# CH32V307VCT6-R1.net
KiCad netlist of a schematic drawn in Altium Designer
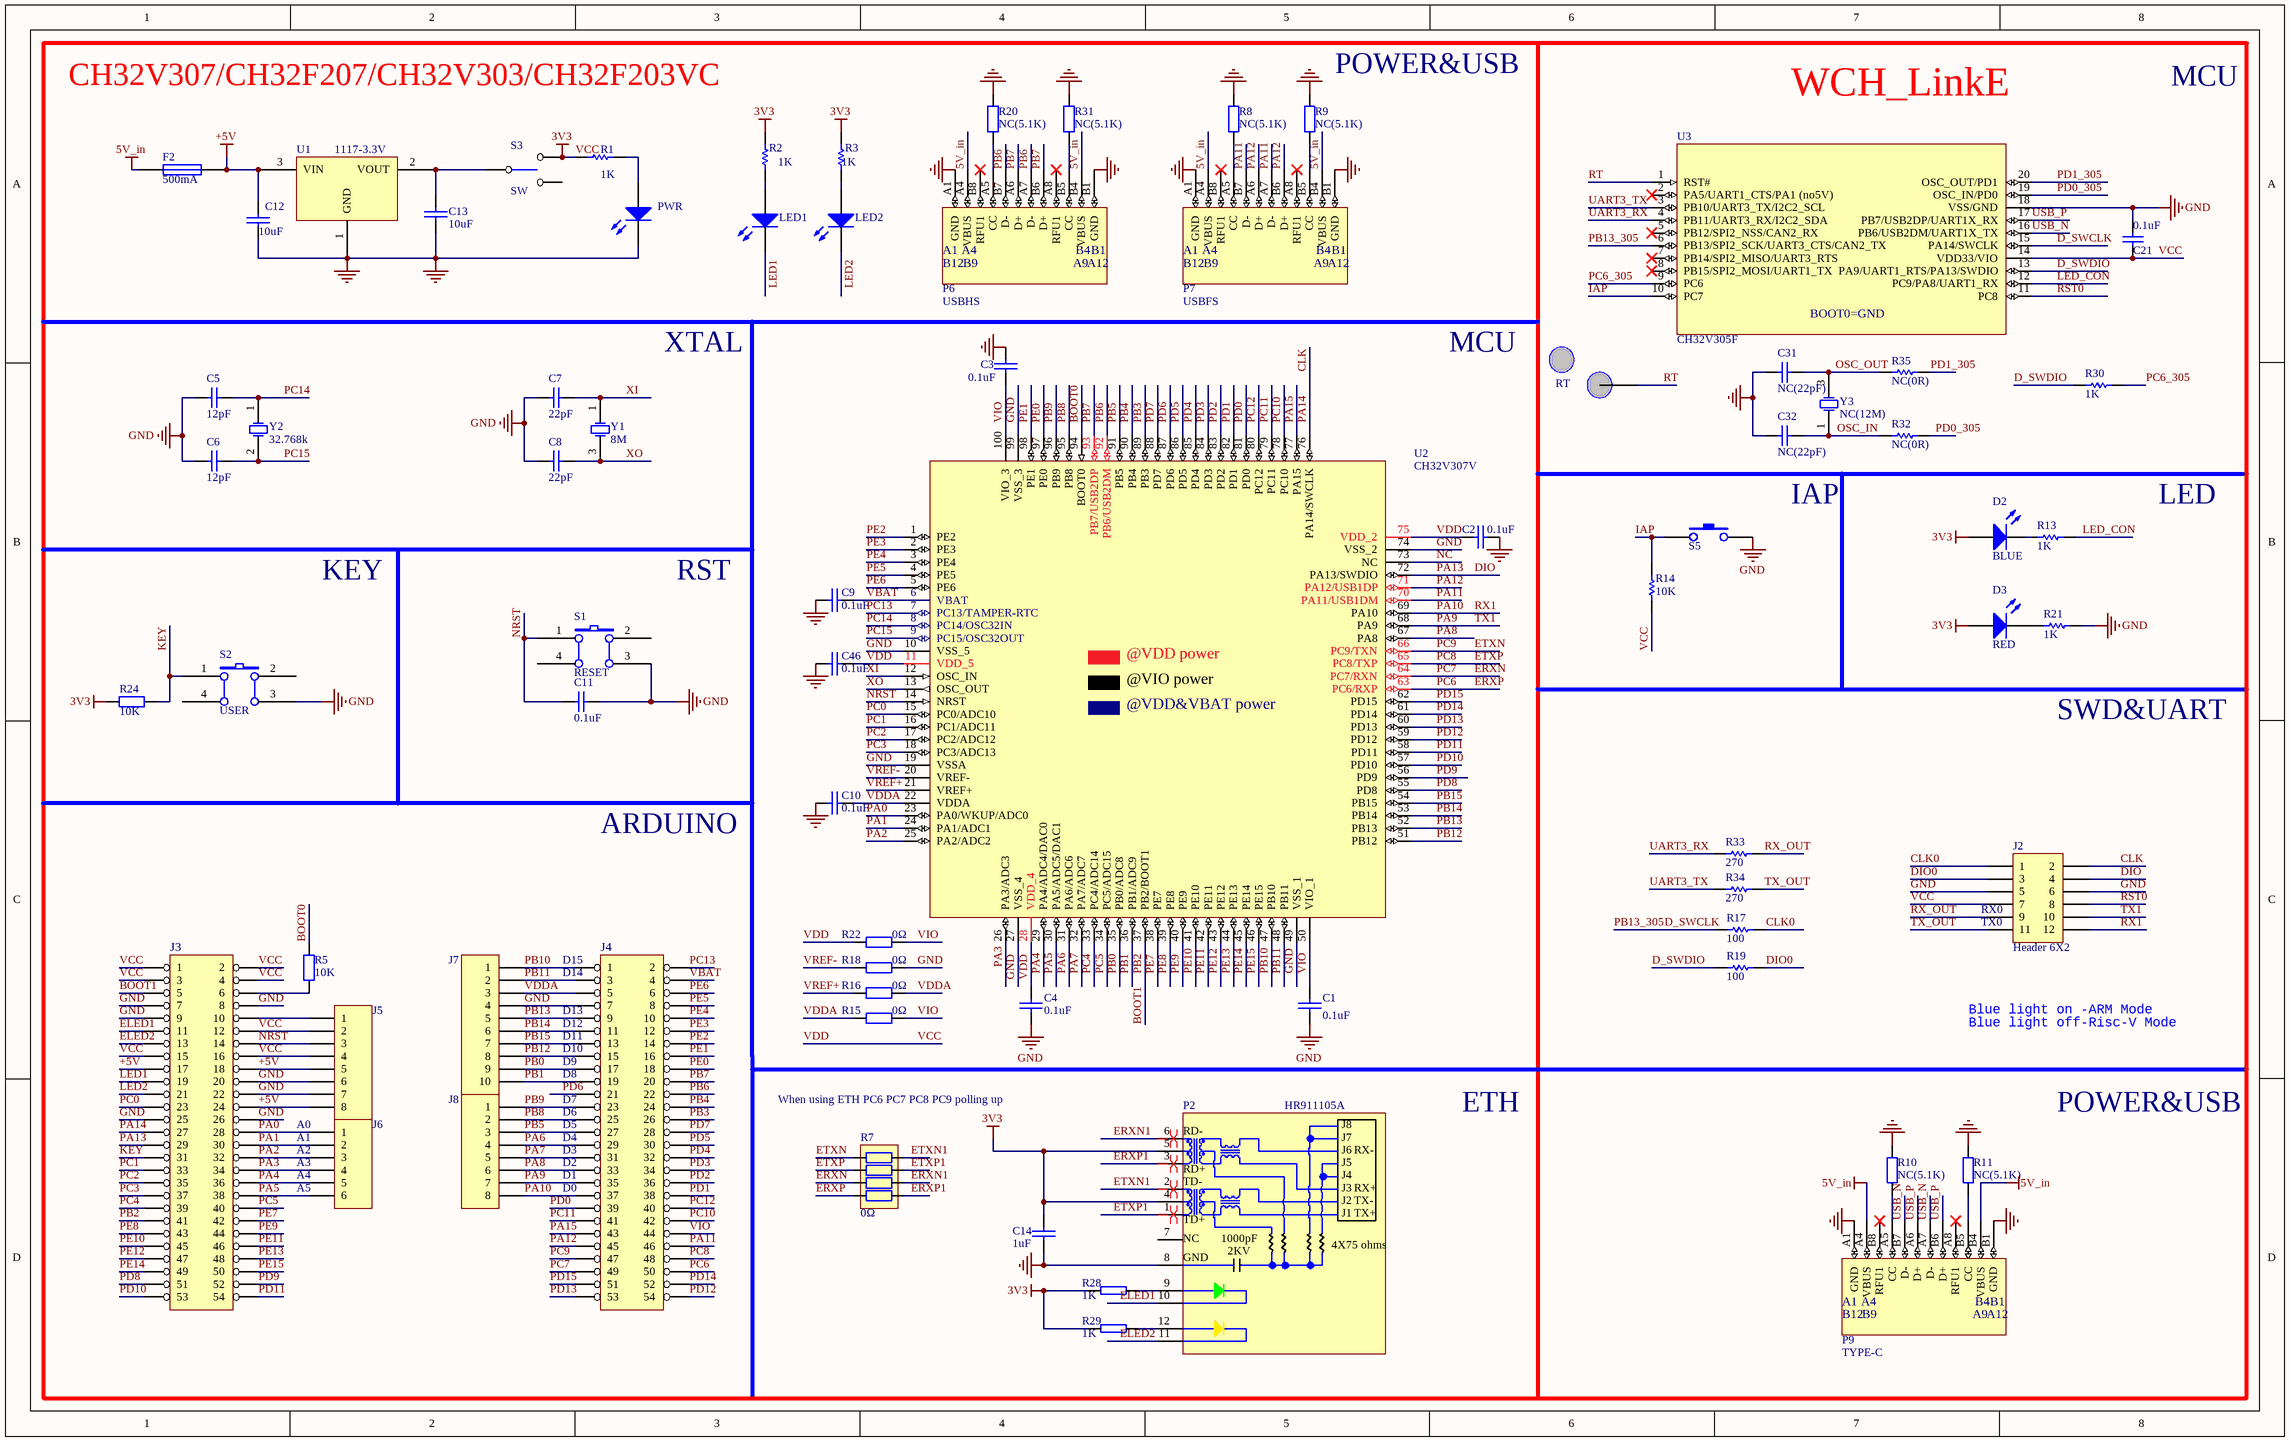
[diagram p0: CH32V307VCT6-R1.SchDoc]

(export (version "E")
  (design (tool "Eeschema 10.0.6"))
  (components
    (comp (ref "C1")
      (value "0.1uF")
      (footprint "0603_C")
      (description "Capacitor")
      (libsource (lib "*") (part "CAP"))
    )
    (comp (ref "C2")
      (value "0.1uF")
      (footprint "0603_C")
      (description "Capacitor")
      (libsource (lib "*") (part "CAP"))
    )
    (comp (ref "C3")
      (value "0.1uF")
      (footprint "0603_C")
      (description "Capacitor")
      (libsource (lib "*") (part "CAP"))
    )
    (comp (ref "C4")
      (value "0.1uF")
      (footprint "0603_C")
      (description "Capacitor")
      (libsource (lib "*") (part "CAP"))
    )
    (comp (ref "C5")
      (value "12pF")
      (footprint "0603_C")
      (description "Capacitor")
      (libsource (lib "Miscellaneous Devices") (part "Cap"))
    )
    (comp (ref "C6")
      (value "12pF")
      (footprint "0603_C")
      (description "Capacitor")
      (libsource (lib "Miscellaneous Devices") (part "Cap"))
    )
    (comp (ref "C7")
      (value "22pF")
      (footprint "0603_C")
      (description "Capacitor")
      (libsource (lib "Miscellaneous Devices") (part "Cap"))
    )
    (comp (ref "C8")
      (value "22pF")
      (footprint "0603_C")
      (description "Capacitor")
      (libsource (lib "Miscellaneous Devices") (part "Cap"))
    )
    (comp (ref "C9")
      (value "0.1uF")
      (footprint "0603_C")
      (description "Capacitor")
      (libsource (lib "*") (part "CAP"))
    )
    (comp (ref "C10")
      (value "0.1uF")
      (footprint "0603_C")
      (description "Capacitor")
      (libsource (lib "*") (part "CAP"))
    )
    (comp (ref "C11")
      (value "0.1uF")
      (footprint "0603_C")
      (description "Capacitor")
      (libsource (lib "Miscellaneous Devices") (part "Cap"))
    )
    (comp (ref "C12")
      (value "10uF")
      (footprint "3216_C")
      (description "Capacitor")
      (libsource (lib "*") (part "CAP"))
    )
    (comp (ref "C13")
      (value "10uF")
      (footprint "3216_C")
      (description "Capacitor")
      (libsource (lib "*") (part "CAP"))
    )
    (comp (ref "C14")
      (value "1uF")
      (footprint "0603_C")
      (description "Capacitor")
      (libsource (lib "*") (part "CAP"))
    )
    (comp (ref "C21")
      (value "0.1uF")
      (footprint "0603_C")
      (description "Capacitor")
      (libsource (lib "Miscellaneous Devices") (part "Cap"))
    )
    (comp (ref "C31")
      (value "NC(22pF)")
      (footprint "0603_C")
      (description "Capacitor")
      (libsource (lib "*") (part "Cap"))
    )
    (comp (ref "C32")
      (value "NC(22pF)")
      (footprint "0603_C")
      (description "Capacitor")
      (libsource (lib "*") (part "Cap"))
    )
    (comp (ref "C46")
      (value "0.1uF")
      (footprint "0603_C")
      (description "Capacitor")
      (libsource (lib "*") (part "CAP"))
    )
    (comp (ref "D2")
      (value "BLUE")
      (footprint "0603+")
      (description "Typical RED, GREEN, YELLOW, AMBER GaAs LED")
      (libsource (lib "MYLIB") (part "D0603"))
    )
    (comp (ref "D3")
      (value "RED")
      (footprint "0603+")
      (description "Typical RED, GREEN, YELLOW, AMBER GaAs LED")
      (libsource (lib "MYLIB") (part "D0603"))
    )
    (comp (ref "F2")
      (value "500mA")
      (footprint "0805")
      (description "Fuse")
      (libsource (lib "*") (part "FUSE1"))
    )
    (comp (ref "J2")
      (value "Header 6X2")
      (footprint "IDC12-2.54mm")
      (description "Header, 6-Pin, Dual row")
      (libsource (lib "Miscellaneous Connectors") (part "Header 6X2"))
    )
    (comp (ref "J3")
      (value "HEADER 27x2")
      (footprint "MYPCB:IDC54-2.54MM")
      (description "Header, 27-Pin, Dual row")
      (libsource (lib "wch_sch_others") (part "HEADER 27x2"))
    )
    (comp (ref "J4")
      (value "HEADER 27x2")
      (footprint "MYPCB:IDC54-2.54MM")
      (description "Header, 27-Pin, Dual row")
      (libsource (lib "wch_sch_others") (part "HEADER 27x2"))
    )
    (comp (ref "J5")
      (value "Header 8")
      (footprint "SIP8-2.54mm")
      (description "Header, 8-Pin")
      (libsource (lib "") (part "Header 8_1"))
    )
    (comp (ref "J6")
      (value "Header 6")
      (footprint "SIP6-2.54MM")
      (description "Header, 6-Pin")
      (libsource (lib "Miscellaneous Connectors") (part "Header 6"))
    )
    (comp (ref "J7")
      (value "Header 10")
      (footprint "SIP10-2.54mm")
      (description "Header, 10-Pin")
      (libsource (lib "Miscellaneous Connectors") (part "Header 10"))
    )
    (comp (ref "J8")
      (value "Header 8")
      (footprint "SIP8-2.54mm")
      (description "Header, 8-Pin")
      (libsource (lib "Miscellaneous Connectors") (part "Header 8"))
    )
    (comp (ref "LED1")
      (value "LED1   blue")
      (footprint "0603+")
      (description "Typical INFRARED GaAs LED")
      (libsource (lib "Miscellaneous Devices") (part "LED0"))
    )
    (comp (ref "LED2")
      (value "LED2  blue")
      (footprint "0603+")
      (description "Typical INFRARED GaAs LED")
      (libsource (lib "Miscellaneous Devices") (part "LED0"))
    )
    (comp (ref "P2") (value "HR911105A") (footprint "HR911105A") (libsource (lib "*") (part "HR911105A")))
    (comp (ref "P6")
      (value "USBHS")
      (footprint "TYPE-C-Receptacle-2.0")
      (libsource (lib "*") (part "TYPE-C1"))
    )
    (comp (ref "P7")
      (value "USBFS")
      (footprint "TYPE-C-Receptacle-2.0")
      (libsource (lib "*") (part "TYPE-C1"))
    )
    (comp (ref "P9")
      (value "TYPE-C")
      (footprint "TYPE-C-Receptacle-2.0")
      (libsource (lib "*") (part "TYPE-C1"))
    )
    (comp (ref "PWR")
      (value "POWER  red")
      (footprint "0603+")
      (description "Typical INFRARED GaAs LED")
      (libsource (lib "Miscellaneous Devices") (part "LED0"))
    )
    (comp (ref "R1")
      (value "1K")
      (footprint "0603")
      (description "Semiconductor Resistor")
      (libsource (lib "Miscellaneous Devices") (part "Res Semi"))
    )
    (comp (ref "R2")
      (value "1K")
      (footprint "0603")
      (description "Semiconductor Resistor")
      (libsource (lib "Miscellaneous Devices") (part "Res Semi"))
    )
    (comp (ref "R3")
      (value "1K")
      (footprint "0603")
      (description "Semiconductor Resistor")
      (libsource (lib "Miscellaneous Devices") (part "Res Semi"))
    )
    (comp (ref "R5")
      (value "10K")
      (footprint "0603")
      (description "Resistor")
      (libsource (lib "Miscellaneous Devices") (part "Res2"))
    )
    (comp (ref "R7")
      (value "0Ω")
      (footprint "RCA-8P4R-0603")
      (description "贴片网络排阻")
      (libsource (lib "wch_sch_others") (part "R-8P4R"))
    )
    (comp (ref "R8")
      (value "NC(5.1K)")
      (footprint "0603")
      (description "Resistor")
      (libsource (lib "") (part "Res2_1"))
    )
    (comp (ref "R9")
      (value "NC(5.1K)")
      (footprint "0603")
      (description "Resistor")
      (libsource (lib "") (part "Res2_1"))
    )
    (comp (ref "R10")
      (value "NC(5.1K)")
      (footprint "0603")
      (description "Resistor")
      (libsource (lib "Miscellaneous Devices") (part "Res2"))
    )
    (comp (ref "R11")
      (value "NC(5.1K)")
      (footprint "0603")
      (description "Resistor")
      (libsource (lib "Miscellaneous Devices") (part "Res2"))
    )
    (comp (ref "R13")
      (value "1K")
      (footprint "0603")
      (description "Resistor")
      (libsource (lib "MYLIB") (part "0603-1"))
    )
    (comp (ref "R14")
      (value "10K")
      (footprint "0603")
      (description "Resistor")
      (libsource (lib "MYLIB") (part "0603-1"))
    )
    (comp (ref "R15")
      (value "0Ω")
      (footprint "0603")
      (description "Resistor")
      (libsource (lib "") (part "Res2_2"))
    )
    (comp (ref "R16")
      (value "0Ω")
      (footprint "0603")
      (description "Resistor")
      (libsource (lib "") (part "Res2_2"))
    )
    (comp (ref "R17")
      (value "100")
      (footprint "0603")
      (description "Resistor")
      (libsource (lib "MYLIB") (part "0603-1"))
    )
    (comp (ref "R18")
      (value "0Ω")
      (footprint "0603")
      (description "Resistor")
      (libsource (lib "") (part "Res2_2"))
    )
    (comp (ref "R19")
      (value "100")
      (footprint "0603")
      (description "Resistor")
      (libsource (lib "MYLIB") (part "0603-1"))
    )
    (comp (ref "R20")
      (value "NC(5.1K)")
      (footprint "0603")
      (description "Resistor")
      (libsource (lib "") (part "Res2_1"))
    )
    (comp (ref "R21")
      (value "1K")
      (footprint "0603")
      (description "Resistor")
      (libsource (lib "MYLIB") (part "0603-1"))
    )
    (comp (ref "R22")
      (value "0Ω")
      (footprint "0603")
      (description "Resistor")
      (libsource (lib "") (part "Res2_2"))
    )
    (comp (ref "R24")
      (value "10K")
      (footprint "0603")
      (description "Resistor")
      (libsource (lib "") (part "Res2_2"))
    )
    (comp (ref "R28") (value "1K") (footprint "0603") (libsource (lib "wch_sch_others") (part "RES")))
    (comp (ref "R29") (value "1K") (footprint "0603") (libsource (lib "wch_sch_others") (part "RES")))
    (comp (ref "R30")
      (value "1K")
      (footprint "0603")
      (description "Resistor")
      (libsource (lib "MYLIB") (part "0603-1"))
    )
    (comp (ref "R31")
      (value "NC(5.1K)")
      (footprint "0603")
      (description "Resistor")
      (libsource (lib "") (part "Res2_1"))
    )
    (comp (ref "R32")
      (value "NC(0R)")
      (footprint "0603")
      (description "Resistor")
      (libsource (lib "MYLIB") (part "0603-1"))
    )
    (comp (ref "R33")
      (value "270")
      (footprint "0603")
      (description "Resistor")
      (libsource (lib "MYLIB") (part "0603-1"))
    )
    (comp (ref "R34")
      (value "270")
      (footprint "0603")
      (description "Resistor")
      (libsource (lib "MYLIB") (part "0603-1"))
    )
    (comp (ref "R35")
      (value "NC(0R)")
      (footprint "0603")
      (description "Resistor")
      (libsource (lib "MYLIB") (part "0603-1"))
    )
    (comp (ref "RT")
      (value "Testpoint")
      (footprint "TESTPOINT1")
      (description "测试点")
      (libsource (lib "wch_sch_others") (part "Testpoint"))
    )
    (comp (ref "S1")
      (value "RESET")
      (footprint "KEYX")
      (description "SE PUSHBUTTON")
      (libsource (lib "Documents") (part "SW PUSHBUTTON"))
    )
    (comp (ref "S2")
      (value "USER")
      (footprint "KEYX")
      (description "SE PUSHBUTTON")
      (libsource (lib "Documents") (part "SW PUSHBUTTON"))
    )
    (comp (ref "S3") (value "SW") (footprint "SW1") (libsource (lib "MYSCH") (part "SW")))
    (comp (ref "S5") (value "KEY") (footprint "贴片按键") (libsource (lib "*") (part "KEY")))
    (comp (ref "U1")
      (value "1117-3.3V")
      (footprint "SOT-223")
      (libsource (lib "wch_sch_others") (part "1117-3.3V"))
    )
    (comp (ref "U2")
      (value "CH32V307V")
      (footprint "LQFP100")
      (description "RISC-V FPU HD-MCU, 144MHz, USB_480M, USB OTG, 1000M Ethernet MAC, 2*CAN, FSMC+DVP")
      (libsource (lib "CHXXX") (part "CH32V307V"))
    )
    (comp (ref "U3")
      (value "CH32V305F")
      (footprint "TSSOP20")
      (description "RISC-V FPU HD-MCU, 144MHz, USB_480M, CAN, UART*2, SPI")
      (libsource (lib "CHXXX") (part "CH32V305F"))
    )
    (comp (ref "Y1")
      (value "8M")
      (footprint "XT3225")
      (description "Crystal Oscillator")
      (libsource (lib "Miscellaneous Devices") (part "XTAL"))
    )
    (comp (ref "Y2")
      (value "32.768k")
      (footprint "FC-135")
      (description "Crystal Oscillator")
      (libsource (lib "") (part "XTAL_1"))
    )
    (comp (ref "Y3")
      (value "NC(12M)")
      (footprint "XT3225")
      (description "Crystal Oscillator")
      (libsource (lib "*") (part "XTAL"))
    )
  )
  (nets
    (net (code "1") (name "+5V") (class "Default")
      (node (ref "C12") (pin "1") (pinfunction "1_1") (pintype "passive"))
      (node (ref "F2") (pin "2") (pinfunction "2_2") (pintype "passive"))
      (node (ref "J3") (pin "17") (pinfunction "17_17") (pintype "passive"))
      (node (ref "J3") (pin "18") (pinfunction "18_18") (pintype "passive"))
      (node (ref "J3") (pin "24") (pinfunction "24_24") (pintype "passive"))
      (node (ref "J5") (pin "5") (pinfunction "5_5") (pintype "passive"))
      (node (ref "J5") (pin "8") (pinfunction "8_8") (pintype "passive"))
      (node (ref "U1") (pin "3") (pinfunction "VIN_3") (pintype "passive"))
    )
    (net (code "2") (name "/BOOT0") (class "Default")
      (node (ref "R5") (pin "2") (pinfunction "2_2") (pintype "passive"))
      (node (ref "U2") (pin "94") (pinfunction "BOOT0_94") (pintype "input"))
    )
    (net (code "3") (name "/BOOT1") (class "Default")
      (node (ref "J3") (pin "41") (pinfunction "41_41") (pintype "passive"))
      (node (ref "J3") (pin "5") (pinfunction "5_5") (pintype "passive"))
      (node (ref "U2") (pin "37") (pinfunction "PB2/BOOT1_37") (pintype "bidirectional"))
    )
    (net (code "4") (name "/CLK") (class "Default")
      (node (ref "J2") (pin "2") (pinfunction "2_2") (pintype "passive"))
      (node (ref "J3") (pin "27") (pinfunction "27_27") (pintype "passive"))
      (node (ref "U2") (pin "76") (pinfunction "PA14/SWCLK_76") (pintype "bidirectional"))
    )
    (net (code "5") (name "/CLK0") (class "Default")
      (node (ref "J2") (pin "1") (pinfunction "1_1") (pintype "passive"))
      (node (ref "R17") (pin "1") (pinfunction "1_1") (pintype "passive"))
    )
    (net (code "6") (name "/DIO") (class "Default")
      (node (ref "J2") (pin "4") (pinfunction "4_4") (pintype "passive"))
      (node (ref "J3") (pin "29") (pinfunction "29_29") (pintype "passive"))
      (node (ref "U2") (pin "72") (pinfunction "PA13/SWDIO_72") (pintype "bidirectional"))
    )
    (net (code "7") (name "/DIO0") (class "Default")
      (node (ref "J2") (pin "3") (pinfunction "3_3") (pintype "passive"))
      (node (ref "R19") (pin "1") (pinfunction "1_1") (pintype "passive"))
    )
    (net (code "8") (name "/D_SWCLK") (class "Default")
      (node (ref "R17") (pin "2") (pinfunction "2_2") (pintype "passive"))
      (node (ref "U3") (pin "15") (pinfunction "PA14/SWCLK_15") (pintype "bidirectional"))
      (node (ref "U3") (pin "6") (pinfunction "PB13/SPI2_SCK/UART3_CTS/CAN2_TX_6") (pintype "bidirectional"))
    )
    (net (code "9") (name "/D_SWDIO") (class "Default")
      (node (ref "R19") (pin "2") (pinfunction "2_2") (pintype "passive"))
      (node (ref "R30") (pin "1") (pinfunction "1_1") (pintype "passive"))
      (node (ref "U3") (pin "13") (pinfunction "PA9/UART1_RTS/PA13/SWDIO_13") (pintype "bidirectional"))
    )
    (net (code "10") (name "/ELED1") (class "Default")
      (node (ref "J3") (pin "11") (pinfunction "11_11") (pintype "passive"))
      (node (ref "P2") (pin "10") (pintype "passive"))
    )
    (net (code "11") (name "/ELED2") (class "Default")
      (node (ref "J3") (pin "13") (pinfunction "13_13") (pintype "passive"))
      (node (ref "P2") (pin "11") (pintype "passive"))
    )
    (net (code "12") (name "/ERXN") (class "Default")
      (node (ref "J4") (pin "49") (pinfunction "49_49") (pintype "passive"))
      (node (ref "R7") (pin "3") (pinfunction "3_3") (pintype "passive"))
      (node (ref "U2") (pin "64") (pinfunction "PC7/RXN_64") (pintype "bidirectional"))
    )
    (net (code "13") (name "/ERXN1") (class "Default")
      (node (ref "P2") (pin "6") (pintype "passive"))
      (node (ref "R7") (pin "6") (pinfunction "6_6") (pintype "passive"))
    )
    (net (code "14") (name "/ERXP") (class "Default")
      (node (ref "J4") (pin "50") (pinfunction "50_50") (pintype "passive"))
      (node (ref "R7") (pin "4") (pinfunction "4_4") (pintype "passive"))
      (node (ref "U2") (pin "63") (pinfunction "PC6/RXP_63") (pintype "bidirectional"))
    )
    (net (code "15") (name "/ERXP1") (class "Default")
      (node (ref "P2") (pin "3") (pintype "passive"))
      (node (ref "R7") (pin "5") (pinfunction "5_5") (pintype "passive"))
    )
    (net (code "16") (name "/ETXN") (class "Default")
      (node (ref "J4") (pin "47") (pinfunction "47_47") (pintype "passive"))
      (node (ref "R7") (pin "1") (pinfunction "1_1") (pintype "passive"))
      (node (ref "U2") (pin "66") (pinfunction "PC9/TXN_66") (pintype "bidirectional"))
    )
    (net (code "17") (name "/ETXN1") (class "Default")
      (node (ref "P2") (pin "2") (pintype "passive"))
      (node (ref "R7") (pin "8") (pinfunction "8_8") (pintype "passive"))
    )
    (net (code "18") (name "/ETXP") (class "Default")
      (node (ref "J4") (pin "48") (pinfunction "48_48") (pintype "passive"))
      (node (ref "R7") (pin "2") (pinfunction "2_2") (pintype "passive"))
      (node (ref "U2") (pin "65") (pinfunction "PC8/TXP_65") (pintype "bidirectional"))
    )
    (net (code "19") (name "/ETXP1") (class "Default")
      (node (ref "P2") (pin "1") (pintype "passive"))
      (node (ref "R7") (pin "7") (pinfunction "7_7") (pintype "passive"))
    )
    (net (code "20") (name "/IAP") (class "Default")
      (node (ref "R14") (pin "1") (pinfunction "1_1") (pintype "passive"))
      (node (ref "S5") (pin "1") (pinfunction "1_1") (pintype "passive"))
      (node (ref "U3") (pin "10") (pinfunction "PC7_10") (pintype "bidirectional"))
    )
    (net (code "21") (name "/KEY") (class "Default")
      (node (ref "J3") (pin "31") (pinfunction "31_31") (pintype "passive"))
      (node (ref "R24") (pin "1") (pinfunction "1_1") (pintype "passive"))
      (node (ref "S2") (pin "1") (pinfunction "A0_1") (pintype "passive"))
    )
    (net (code "22") (name "/LED1") (class "Default")
      (node (ref "J3") (pin "19") (pinfunction "19_19") (pintype "passive"))
      (node (ref "LED1") (pin "2") (pinfunction "K_2") (pintype "passive"))
    )
    (net (code "23") (name "/LED2") (class "Default")
      (node (ref "J3") (pin "21") (pinfunction "21_21") (pintype "passive"))
      (node (ref "LED2") (pin "2") (pinfunction "K_2") (pintype "passive"))
    )
    (net (code "24") (name "/LED_CON") (class "Default")
      (node (ref "R13") (pin "1") (pinfunction "1_1") (pintype "passive"))
      (node (ref "U3") (pin "12") (pinfunction "PC9/PA8/UART1_RX_12") (pintype "bidirectional"))
    )
    (net (code "25") (name "/NC") (class "Default")
      (node (ref "U2") (pin "73") (pinfunction "NC_73") (pintype "tri_state"))
    )
    (net (code "26") (name "/NRST") (class "Default")
      (node (ref "C11") (pin "2") (pinfunction "2_2") (pintype "passive"))
      (node (ref "J3") (pin "14") (pinfunction "14_14") (pintype "passive"))
      (node (ref "J5") (pin "3") (pinfunction "3_3") (pintype "passive"))
      (node (ref "S1") (pin "1") (pinfunction "A0_1") (pintype "passive"))
      (node (ref "U2") (pin "14") (pinfunction "NRST_14") (pintype "input"))
    )
    (net (code "27") (name "/OSC_IN") (class "Default")
      (node (ref "C32") (pin "2") (pinfunction "2_2") (pintype "passive"))
      (node (ref "R32") (pin "2") (pinfunction "2_2") (pintype "passive"))
      (node (ref "Y3") (pin "1") (pinfunction "OSC1_1") (pintype "passive"))
    )
    (net (code "28") (name "/OSC_OUT") (class "Default")
      (node (ref "C31") (pin "2") (pinfunction "2_2") (pintype "passive"))
      (node (ref "R35") (pin "2") (pinfunction "2_2") (pintype "passive"))
      (node (ref "Y3") (pin "3") (pinfunction "OSC2_3") (pintype "passive"))
    )
    (net (code "29") (name "/PA0") (class "Default")
      (node (ref "J3") (pin "28") (pinfunction "28_28") (pintype "passive"))
      (node (ref "J6") (pin "1") (pinfunction "1_1") (pintype "passive"))
      (node (ref "U2") (pin "23") (pinfunction "PA0/WKUP/ADC0_23") (pintype "bidirectional"))
    )
    (net (code "30") (name "/PA1") (class "Default")
      (node (ref "J3") (pin "30") (pinfunction "30_30") (pintype "passive"))
      (node (ref "J6") (pin "2") (pinfunction "2_2") (pintype "passive"))
      (node (ref "U2") (pin "24") (pinfunction "PA1/ADC1_24") (pintype "bidirectional"))
    )
    (net (code "31") (name "/PA2") (class "Default")
      (node (ref "J3") (pin "32") (pinfunction "32_32") (pintype "passive"))
      (node (ref "J6") (pin "3") (pinfunction "3_3") (pintype "passive"))
      (node (ref "U2") (pin "25") (pinfunction "PA2/ADC2_25") (pintype "bidirectional"))
    )
    (net (code "32") (name "/PA3") (class "Default")
      (node (ref "J3") (pin "34") (pinfunction "34_34") (pintype "passive"))
      (node (ref "J6") (pin "4") (pinfunction "4_4") (pintype "passive"))
      (node (ref "U2") (pin "26") (pinfunction "PA3/ADC3_26") (pintype "bidirectional"))
    )
    (net (code "33") (name "/PA4") (class "Default")
      (node (ref "J3") (pin "36") (pinfunction "36_36") (pintype "passive"))
      (node (ref "J6") (pin "5") (pinfunction "5_5") (pintype "passive"))
      (node (ref "U2") (pin "29") (pinfunction "PA4/ADC4/DAC0_29") (pintype "bidirectional"))
    )
    (net (code "34") (name "/PA5") (class "Default")
      (node (ref "J3") (pin "38") (pinfunction "38_38") (pintype "passive"))
      (node (ref "J6") (pin "6") (pinfunction "6_6") (pintype "passive"))
      (node (ref "U2") (pin "30") (pinfunction "PA5/ADC5/DAC1_30") (pintype "bidirectional"))
    )
    (net (code "35") (name "/PA6") (class "Default")
      (node (ref "J4") (pin "29") (pinfunction "29_29") (pintype "passive"))
      (node (ref "J8") (pin "4") (pinfunction "4_4") (pintype "passive"))
      (node (ref "U2") (pin "31") (pinfunction "PA6/ADC6_31") (pintype "bidirectional"))
    )
    (net (code "36") (name "/PA7") (class "Default")
      (node (ref "J4") (pin "31") (pinfunction "31_31") (pintype "passive"))
      (node (ref "J8") (pin "5") (pinfunction "5_5") (pintype "passive"))
      (node (ref "U2") (pin "32") (pinfunction "PA7/ADC7_32") (pintype "bidirectional"))
    )
    (net (code "37") (name "/PA8") (class "Default")
      (node (ref "J4") (pin "33") (pinfunction "33_33") (pintype "passive"))
      (node (ref "J8") (pin "6") (pinfunction "6_6") (pintype "passive"))
      (node (ref "U2") (pin "67") (pinfunction "PA8_67") (pintype "bidirectional"))
    )
    (net (code "38") (name "/PA9") (class "Default")
      (node (ref "J2") (pin "10") (pinfunction "10_10") (pintype "passive"))
      (node (ref "J4") (pin "35") (pinfunction "35_35") (pintype "passive"))
      (node (ref "J8") (pin "7") (pinfunction "7_7") (pintype "passive"))
      (node (ref "U2") (pin "68") (pinfunction "PA9_68") (pintype "bidirectional"))
    )
    (net (code "39") (name "/PA10") (class "Default")
      (node (ref "J2") (pin "12") (pinfunction "12_12") (pintype "passive"))
      (node (ref "J4") (pin "37") (pinfunction "37_37") (pintype "passive"))
      (node (ref "J8") (pin "8") (pinfunction "8_8") (pintype "passive"))
      (node (ref "U2") (pin "69") (pinfunction "PA10_69") (pintype "bidirectional"))
    )
    (net (code "40") (name "/PA11") (class "Default")
      (node (ref "J4") (pin "46") (pinfunction "46_46") (pintype "passive"))
      (node (ref "P7") (pin "A7") (pinfunction "D-_A7") (pintype "bidirectional"))
      (node (ref "P7") (pin "B7") (pinfunction "D-_B7") (pintype "bidirectional"))
      (node (ref "U2") (pin "70") (pinfunction "PA11/USB1DM_70") (pintype "bidirectional"))
    )
    (net (code "41") (name "/PA12") (class "Default")
      (node (ref "J4") (pin "45") (pinfunction "45_45") (pintype "passive"))
      (node (ref "P7") (pin "A6") (pinfunction "D+_A6") (pintype "bidirectional"))
      (node (ref "P7") (pin "B6") (pinfunction "D+_B6") (pintype "bidirectional"))
      (node (ref "U2") (pin "71") (pinfunction "PA12/USB1DP_71") (pintype "bidirectional"))
    )
    (net (code "42") (name "/PA15") (class "Default")
      (node (ref "J4") (pin "43") (pinfunction "43_43") (pintype "passive"))
      (node (ref "U2") (pin "77") (pinfunction "PA15_77") (pintype "bidirectional"))
    )
    (net (code "43") (name "/PB0") (class "Default")
      (node (ref "J4") (pin "17") (pinfunction "17_17") (pintype "passive"))
      (node (ref "J7") (pin "9") (pinfunction "9_9") (pintype "passive"))
      (node (ref "U2") (pin "35") (pinfunction "PB0/ADC8_35") (pintype "bidirectional"))
    )
    (net (code "44") (name "/PB1") (class "Default")
      (node (ref "J4") (pin "19") (pinfunction "19_19") (pintype "passive"))
      (node (ref "J7") (pin "10") (pinfunction "10_10") (pintype "passive"))
      (node (ref "U2") (pin "36") (pinfunction "PB1/ADC9_36") (pintype "bidirectional"))
    )
    (net (code "45") (name "/PB3") (class "Default")
      (node (ref "J4") (pin "26") (pinfunction "26_26") (pintype "passive"))
      (node (ref "U2") (pin "89") (pinfunction "PB3_89") (pintype "bidirectional"))
    )
    (net (code "46") (name "/PB4") (class "Default")
      (node (ref "J4") (pin "24") (pinfunction "24_24") (pintype "passive"))
      (node (ref "U2") (pin "90") (pinfunction "PB4_90") (pintype "bidirectional"))
    )
    (net (code "47") (name "/PB5") (class "Default")
      (node (ref "J4") (pin "27") (pinfunction "27_27") (pintype "passive"))
      (node (ref "J8") (pin "3") (pinfunction "3_3") (pintype "passive"))
      (node (ref "U2") (pin "91") (pinfunction "PB5_91") (pintype "bidirectional"))
    )
    (net (code "48") (name "/PB6") (class "Default")
      (node (ref "J4") (pin "22") (pinfunction "22_22") (pintype "passive"))
      (node (ref "P6") (pin "A7") (pinfunction "D-_A7") (pintype "bidirectional"))
      (node (ref "P6") (pin "B7") (pinfunction "D-_B7") (pintype "bidirectional"))
      (node (ref "U2") (pin "92") (pinfunction "PB6/USB2DM_92") (pintype "bidirectional"))
    )
    (net (code "49") (name "/PB7") (class "Default")
      (node (ref "J4") (pin "20") (pinfunction "20_20") (pintype "passive"))
      (node (ref "P6") (pin "A6") (pinfunction "D+_A6") (pintype "bidirectional"))
      (node (ref "P6") (pin "B6") (pinfunction "D+_B6") (pintype "bidirectional"))
      (node (ref "U2") (pin "93") (pinfunction "PB7/USB2DP_93") (pintype "bidirectional"))
    )
    (net (code "50") (name "/PB8") (class "Default")
      (node (ref "J4") (pin "25") (pinfunction "25_25") (pintype "passive"))
      (node (ref "J8") (pin "2") (pinfunction "2_2") (pintype "passive"))
      (node (ref "U2") (pin "95") (pinfunction "PB8_95") (pintype "bidirectional"))
    )
    (net (code "51") (name "/PB9") (class "Default")
      (node (ref "J4") (pin "23") (pinfunction "23_23") (pintype "passive"))
      (node (ref "J8") (pin "1") (pinfunction "1_1") (pintype "passive"))
      (node (ref "U2") (pin "96") (pinfunction "PB9_96") (pintype "bidirectional"))
    )
    (net (code "52") (name "/PB10") (class "Default")
      (node (ref "J4") (pin "1") (pinfunction "1_1") (pintype "passive"))
      (node (ref "J7") (pin "1") (pinfunction "1_1") (pintype "passive"))
      (node (ref "U2") (pin "47") (pinfunction "PB10_47") (pintype "bidirectional"))
    )
    (net (code "53") (name "/PB11") (class "Default")
      (node (ref "J4") (pin "3") (pinfunction "3_3") (pintype "passive"))
      (node (ref "J7") (pin "2") (pinfunction "2_2") (pintype "passive"))
      (node (ref "U2") (pin "48") (pinfunction "PB11_48") (pintype "bidirectional"))
    )
    (net (code "54") (name "/PB12") (class "Default")
      (node (ref "J4") (pin "15") (pinfunction "15_15") (pintype "passive"))
      (node (ref "J7") (pin "8") (pinfunction "8_8") (pintype "passive"))
      (node (ref "U2") (pin "51") (pinfunction "PB12_51") (pintype "bidirectional"))
    )
    (net (code "55") (name "/PB13") (class "Default")
      (node (ref "J4") (pin "9") (pinfunction "9_9") (pintype "passive"))
      (node (ref "J7") (pin "5") (pinfunction "5_5") (pintype "passive"))
      (node (ref "U2") (pin "52") (pinfunction "PB13_52") (pintype "bidirectional"))
    )
    (net (code "56") (name "/PB14") (class "Default")
      (node (ref "J4") (pin "11") (pinfunction "11_11") (pintype "passive"))
      (node (ref "J7") (pin "6") (pinfunction "6_6") (pintype "passive"))
      (node (ref "U2") (pin "53") (pinfunction "PB14_53") (pintype "bidirectional"))
    )
    (net (code "57") (name "/PB15") (class "Default")
      (node (ref "J4") (pin "13") (pinfunction "13_13") (pintype "passive"))
      (node (ref "J7") (pin "7") (pinfunction "7_7") (pintype "passive"))
      (node (ref "U2") (pin "54") (pinfunction "PB15_54") (pintype "bidirectional"))
    )
    (net (code "58") (name "/PC0") (class "Default")
      (node (ref "J3") (pin "23") (pinfunction "23_23") (pintype "passive"))
      (node (ref "U2") (pin "15") (pinfunction "PC0/ADC10_15") (pintype "bidirectional"))
    )
    (net (code "59") (name "/PC1") (class "Default")
      (node (ref "J3") (pin "33") (pinfunction "33_33") (pintype "passive"))
      (node (ref "U2") (pin "16") (pinfunction "PC1/ADC11_16") (pintype "bidirectional"))
    )
    (net (code "60") (name "/PC2") (class "Default")
      (node (ref "J3") (pin "35") (pinfunction "35_35") (pintype "passive"))
      (node (ref "U2") (pin "17") (pinfunction "PC2/ADC12_17") (pintype "bidirectional"))
    )
    (net (code "61") (name "/PC3") (class "Default")
      (node (ref "J3") (pin "37") (pinfunction "37_37") (pintype "passive"))
      (node (ref "U2") (pin "18") (pinfunction "PC3/ADC13_18") (pintype "bidirectional"))
    )
    (net (code "62") (name "/PC4") (class "Default")
      (node (ref "J3") (pin "39") (pinfunction "39_39") (pintype "passive"))
      (node (ref "U2") (pin "33") (pinfunction "PC4/ADC14_33") (pintype "bidirectional"))
    )
    (net (code "63") (name "/PC5") (class "Default")
      (node (ref "J3") (pin "40") (pinfunction "40_40") (pintype "passive"))
      (node (ref "U2") (pin "34") (pinfunction "PC5/ADC15_34") (pintype "bidirectional"))
    )
    (net (code "64") (name "/PC6_305") (class "Default")
      (node (ref "R30") (pin "2") (pinfunction "2_2") (pintype "passive"))
      (node (ref "U3") (pin "9") (pinfunction "PC6_9") (pintype "bidirectional"))
    )
    (net (code "65") (name "/PC10") (class "Default")
      (node (ref "J4") (pin "42") (pinfunction "42_42") (pintype "passive"))
      (node (ref "U2") (pin "78") (pinfunction "PC10_78") (pintype "bidirectional"))
    )
    (net (code "66") (name "/PC11") (class "Default")
      (node (ref "J4") (pin "41") (pinfunction "41_41") (pintype "passive"))
      (node (ref "U2") (pin "79") (pinfunction "PC11_79") (pintype "bidirectional"))
    )
    (net (code "67") (name "/PC12") (class "Default")
      (node (ref "J4") (pin "40") (pinfunction "40_40") (pintype "passive"))
      (node (ref "U2") (pin "80") (pinfunction "PC12_80") (pintype "bidirectional"))
    )
    (net (code "68") (name "/PC13") (class "Default")
      (node (ref "J4") (pin "2") (pinfunction "2_2") (pintype "passive"))
      (node (ref "U2") (pin "7") (pinfunction "PC13/TAMPER-RTC_7") (pintype "bidirectional"))
    )
    (net (code "69") (name "/PC14") (class "Default")
      (node (ref "C5") (pin "1") (pinfunction "1_1") (pintype "passive"))
      (node (ref "U2") (pin "8") (pinfunction "PC14/OSC32IN_8") (pintype "bidirectional"))
      (node (ref "Y2") (pin "1") (pinfunction "OSC1_1") (pintype "passive"))
    )
    (net (code "70") (name "/PC15") (class "Default")
      (node (ref "C6") (pin "1") (pinfunction "1_1") (pintype "passive"))
      (node (ref "U2") (pin "9") (pinfunction "PC15/OSC32OUT_9") (pintype "bidirectional"))
      (node (ref "Y2") (pin "2") (pinfunction "OSC2_2") (pintype "passive"))
    )
    (net (code "71") (name "/PD0") (class "Default")
      (node (ref "J4") (pin "39") (pinfunction "39_39") (pintype "passive"))
      (node (ref "U2") (pin "81") (pinfunction "PD0_81") (pintype "bidirectional"))
    )
    (net (code "72") (name "/PD0_305") (class "Default")
      (node (ref "R32") (pin "1") (pinfunction "1_1") (pintype "passive"))
      (node (ref "U3") (pin "19") (pinfunction "OSC_IN/PD0_19") (pintype "bidirectional"))
    )
    (net (code "73") (name "/PD1") (class "Default")
      (node (ref "J4") (pin "38") (pinfunction "38_38") (pintype "passive"))
      (node (ref "U2") (pin "82") (pinfunction "PD1_82") (pintype "bidirectional"))
    )
    (net (code "74") (name "/PD1_305") (class "Default")
      (node (ref "R35") (pin "1") (pinfunction "1_1") (pintype "passive"))
      (node (ref "U3") (pin "20") (pinfunction "OSC_OUT/PD1_20") (pintype "bidirectional"))
    )
    (net (code "75") (name "/PD2") (class "Default")
      (node (ref "J4") (pin "36") (pinfunction "36_36") (pintype "passive"))
      (node (ref "U2") (pin "83") (pinfunction "PD2_83") (pintype "bidirectional"))
    )
    (net (code "76") (name "/PD3") (class "Default")
      (node (ref "J4") (pin "34") (pinfunction "34_34") (pintype "passive"))
      (node (ref "U2") (pin "84") (pinfunction "PD3_84") (pintype "bidirectional"))
    )
    (net (code "77") (name "/PD4") (class "Default")
      (node (ref "J4") (pin "32") (pinfunction "32_32") (pintype "passive"))
      (node (ref "U2") (pin "85") (pinfunction "PD4_85") (pintype "bidirectional"))
    )
    (net (code "78") (name "/PD5") (class "Default")
      (node (ref "J4") (pin "30") (pinfunction "30_30") (pintype "passive"))
      (node (ref "U2") (pin "86") (pinfunction "PD5_86") (pintype "bidirectional"))
    )
    (net (code "79") (name "/PD6") (class "Default")
      (node (ref "J4") (pin "21") (pinfunction "21_21") (pintype "passive"))
      (node (ref "U2") (pin "87") (pinfunction "PD6_87") (pintype "bidirectional"))
    )
    (net (code "80") (name "/PD7") (class "Default")
      (node (ref "J4") (pin "28") (pinfunction "28_28") (pintype "passive"))
      (node (ref "U2") (pin "88") (pinfunction "PD7_88") (pintype "bidirectional"))
    )
    (net (code "81") (name "/PD8") (class "Default")
      (node (ref "J3") (pin "51") (pinfunction "51_51") (pintype "passive"))
      (node (ref "U2") (pin "55") (pinfunction "PD8_55") (pintype "bidirectional"))
    )
    (net (code "82") (name "/PD9") (class "Default")
      (node (ref "J3") (pin "52") (pinfunction "52_52") (pintype "passive"))
      (node (ref "U2") (pin "56") (pinfunction "PD9_56") (pintype "bidirectional"))
    )
    (net (code "83") (name "/PD10") (class "Default")
      (node (ref "J3") (pin "53") (pinfunction "53_53") (pintype "passive"))
      (node (ref "U2") (pin "57") (pinfunction "PD10_57") (pintype "bidirectional"))
    )
    (net (code "84") (name "/PD11") (class "Default")
      (node (ref "J3") (pin "54") (pinfunction "54_54") (pintype "passive"))
      (node (ref "U2") (pin "58") (pinfunction "PD11_58") (pintype "bidirectional"))
    )
    (net (code "85") (name "/PD12") (class "Default")
      (node (ref "J4") (pin "54") (pinfunction "54_54") (pintype "passive"))
      (node (ref "U2") (pin "59") (pinfunction "PD12_59") (pintype "bidirectional"))
    )
    (net (code "86") (name "/PD13") (class "Default")
      (node (ref "J4") (pin "53") (pinfunction "53_53") (pintype "passive"))
      (node (ref "U2") (pin "60") (pinfunction "PD13_60") (pintype "bidirectional"))
    )
    (net (code "87") (name "/PD14") (class "Default")
      (node (ref "J4") (pin "52") (pinfunction "52_52") (pintype "passive"))
      (node (ref "U2") (pin "61") (pinfunction "PD14_61") (pintype "bidirectional"))
    )
    (net (code "88") (name "/PD15") (class "Default")
      (node (ref "J4") (pin "51") (pinfunction "51_51") (pintype "passive"))
      (node (ref "U2") (pin "62") (pinfunction "PD15_62") (pintype "bidirectional"))
    )
    (net (code "89") (name "/PE0") (class "Default")
      (node (ref "J4") (pin "18") (pinfunction "18_18") (pintype "passive"))
      (node (ref "U2") (pin "97") (pinfunction "PE0_97") (pintype "bidirectional"))
    )
    (net (code "90") (name "/PE1") (class "Default")
      (node (ref "J4") (pin "16") (pinfunction "16_16") (pintype "passive"))
      (node (ref "U2") (pin "98") (pinfunction "PE1_98") (pintype "bidirectional"))
    )
    (net (code "91") (name "/PE2") (class "Default")
      (node (ref "J4") (pin "14") (pinfunction "14_14") (pintype "passive"))
      (node (ref "U2") (pin "1") (pinfunction "PE2_1") (pintype "bidirectional"))
    )
    (net (code "92") (name "/PE3") (class "Default")
      (node (ref "J4") (pin "12") (pinfunction "12_12") (pintype "passive"))
      (node (ref "U2") (pin "2") (pinfunction "PE3_2") (pintype "bidirectional"))
    )
    (net (code "93") (name "/PE4") (class "Default")
      (node (ref "J4") (pin "10") (pinfunction "10_10") (pintype "passive"))
      (node (ref "U2") (pin "3") (pinfunction "PE4_3") (pintype "bidirectional"))
    )
    (net (code "94") (name "/PE5") (class "Default")
      (node (ref "J4") (pin "8") (pinfunction "8_8") (pintype "passive"))
      (node (ref "U2") (pin "4") (pinfunction "PE5_4") (pintype "bidirectional"))
    )
    (net (code "95") (name "/PE6") (class "Default")
      (node (ref "J4") (pin "6") (pinfunction "6_6") (pintype "passive"))
      (node (ref "U2") (pin "5") (pinfunction "PE6_5") (pintype "bidirectional"))
    )
    (net (code "96") (name "/PE7") (class "Default")
      (node (ref "J3") (pin "42") (pinfunction "42_42") (pintype "passive"))
      (node (ref "U2") (pin "38") (pinfunction "PE7_38") (pintype "bidirectional"))
    )
    (net (code "97") (name "/PE8") (class "Default")
      (node (ref "J3") (pin "43") (pinfunction "43_43") (pintype "passive"))
      (node (ref "U2") (pin "39") (pinfunction "PE8_39") (pintype "bidirectional"))
    )
    (net (code "98") (name "/PE9") (class "Default")
      (node (ref "J3") (pin "44") (pinfunction "44_44") (pintype "passive"))
      (node (ref "U2") (pin "40") (pinfunction "PE9_40") (pintype "bidirectional"))
    )
    (net (code "99") (name "/PE10") (class "Default")
      (node (ref "J3") (pin "45") (pinfunction "45_45") (pintype "passive"))
      (node (ref "U2") (pin "41") (pinfunction "PE10_41") (pintype "bidirectional"))
    )
    (net (code "100") (name "/PE11") (class "Default")
      (node (ref "J3") (pin "46") (pinfunction "46_46") (pintype "passive"))
      (node (ref "U2") (pin "42") (pinfunction "PE11_42") (pintype "bidirectional"))
    )
    (net (code "101") (name "/PE12") (class "Default")
      (node (ref "J3") (pin "47") (pinfunction "47_47") (pintype "passive"))
      (node (ref "U2") (pin "43") (pinfunction "PE12_43") (pintype "bidirectional"))
    )
    (net (code "102") (name "/PE13") (class "Default")
      (node (ref "J3") (pin "48") (pinfunction "48_48") (pintype "passive"))
      (node (ref "U2") (pin "44") (pinfunction "PE13_44") (pintype "bidirectional"))
    )
    (net (code "103") (name "/PE14") (class "Default")
      (node (ref "J3") (pin "49") (pinfunction "49_49") (pintype "passive"))
      (node (ref "U2") (pin "45") (pinfunction "PE14_45") (pintype "bidirectional"))
    )
    (net (code "104") (name "/PE15") (class "Default")
      (node (ref "J3") (pin "50") (pinfunction "50_50") (pintype "passive"))
      (node (ref "U2") (pin "46") (pinfunction "PE15_46") (pintype "bidirectional"))
    )
    (net (code "105") (name "/RST0") (class "Default")
      (node (ref "J2") (pin "8") (pinfunction "8_8") (pintype "passive"))
      (node (ref "U3") (pin "11") (pinfunction "PC8_11") (pintype "bidirectional"))
    )
    (net (code "106") (name "/RT") (class "Default")
      (node (ref "RT") (pin "1") (pinfunction "point_1") (pintype "passive"))
      (node (ref "U3") (pin "1") (pinfunction "RST#_1") (pintype "input"))
    )
    (net (code "107") (name "/RX_OUT") (class "Default")
      (node (ref "J2") (pin "9") (pinfunction "9_9") (pintype "passive"))
      (node (ref "R33") (pin "1") (pinfunction "1_1") (pintype "passive"))
    )
    (net (code "108") (name "/TX_OUT") (class "Default")
      (node (ref "J2") (pin "11") (pinfunction "11_11") (pintype "passive"))
      (node (ref "R34") (pin "1") (pinfunction "1_1") (pintype "passive"))
    )
    (net (code "109") (name "/UART3_RX") (class "Default")
      (node (ref "R33") (pin "2") (pinfunction "2_2") (pintype "passive"))
      (node (ref "U3") (pin "4") (pinfunction "PB11/UART3_RX/I2C2_SDA_4") (pintype "bidirectional"))
    )
    (net (code "110") (name "/UART3_TX") (class "Default")
      (node (ref "R34") (pin "2") (pinfunction "2_2") (pintype "passive"))
      (node (ref "U3") (pin "3") (pinfunction "PB10/UART3_TX/I2C2_SCL_3") (pintype "bidirectional"))
    )
    (net (code "111") (name "/USB_N") (class "Default")
      (node (ref "P9") (pin "A7") (pinfunction "D-_A7") (pintype "bidirectional"))
      (node (ref "P9") (pin "B7") (pinfunction "D-_B7") (pintype "bidirectional"))
      (node (ref "U3") (pin "16") (pinfunction "PB6/USB2DM/UART1X_TX_16") (pintype "bidirectional"))
    )
    (net (code "112") (name "/USB_P") (class "Default")
      (node (ref "P9") (pin "A6") (pinfunction "D+_A6") (pintype "bidirectional"))
      (node (ref "P9") (pin "B6") (pinfunction "D+_B6") (pintype "bidirectional"))
      (node (ref "U3") (pin "17") (pinfunction "PB7/USB2DP/UART1X_RX_17") (pintype "bidirectional"))
    )
    (net (code "113") (name "/VBAT") (class "Default")
      (node (ref "C9") (pin "2") (pinfunction "2_2") (pintype "passive"))
      (node (ref "J4") (pin "4") (pinfunction "4_4") (pintype "passive"))
      (node (ref "U2") (pin "6") (pinfunction "VBAT_6") (pintype "power_in"))
    )
    (net (code "114") (name "/VDDA") (class "Default")
      (node (ref "C10") (pin "2") (pinfunction "2_2") (pintype "passive"))
      (node (ref "J4") (pin "5") (pinfunction "5_5") (pintype "passive"))
      (node (ref "J7") (pin "3") (pinfunction "3_3") (pintype "passive"))
      (node (ref "R15") (pin "2") (pinfunction "2_2") (pintype "passive"))
      (node (ref "R16") (pin "1") (pinfunction "1_1") (pintype "passive"))
      (node (ref "U2") (pin "22") (pinfunction "VDDA_22") (pintype "power_in"))
    )
    (net (code "115") (name "/VIO") (class "Default")
      (node (ref "C1") (pin "2") (pinfunction "2_2") (pintype "passive"))
      (node (ref "C3") (pin "1") (pinfunction "1_1") (pintype "passive"))
      (node (ref "J4") (pin "44") (pinfunction "44_44") (pintype "passive"))
      (node (ref "R15") (pin "1") (pinfunction "1_1") (pintype "passive"))
      (node (ref "R22") (pin "1") (pinfunction "1_1") (pintype "passive"))
      (node (ref "U2") (pin "100") (pinfunction "VIO_3_100") (pintype "power_in"))
      (node (ref "U2") (pin "50") (pinfunction "VIO_1_50") (pintype "power_in"))
    )
    (net (code "116") (name "/VREF+") (class "Default")
      (node (ref "R16") (pin "2") (pinfunction "2_2") (pintype "passive"))
      (node (ref "U2") (pin "21") (pinfunction "VREF+_21") (pintype "power_in"))
    )
    (net (code "117") (name "/VREF-") (class "Default")
      (node (ref "R18") (pin "2") (pinfunction "2_2") (pintype "passive"))
      (node (ref "U2") (pin "20") (pinfunction "VREF-_20") (pintype "power_in"))
    )
    (net (code "118") (name "/XI") (class "Default")
      (node (ref "C7") (pin "2") (pinfunction "2_2") (pintype "passive"))
      (node (ref "U2") (pin "12") (pinfunction "OSC_IN_12") (pintype "input"))
      (node (ref "Y1") (pin "1") (pinfunction "OSC1_1") (pintype "passive"))
    )
    (net (code "119") (name "/XO") (class "Default")
      (node (ref "C8") (pin "2") (pinfunction "2_2") (pintype "passive"))
      (node (ref "U2") (pin "13") (pinfunction "OSC_OUT_13") (pintype "output"))
      (node (ref "Y1") (pin "3") (pinfunction "OSC2_3") (pintype "passive"))
    )
    (net (code "120") (name "3V3") (class "Default")
      (node (ref "C14") (pin "2") (pinfunction "2_2") (pintype "passive"))
      (node (ref "C2") (pin "2") (pinfunction "2_2") (pintype "passive"))
      (node (ref "C21") (pin "1") (pinfunction "1_1") (pintype "passive"))
      (node (ref "C4") (pin "2") (pinfunction "2_2") (pintype "passive"))
      (node (ref "C46") (pin "1") (pinfunction "1_1") (pintype "passive"))
      (node (ref "D2") (pin "1") (pinfunction "A_1") (pintype "passive"))
      (node (ref "D3") (pin "1") (pinfunction "A_1") (pintype "passive"))
      (node (ref "J2") (pin "7") (pinfunction "7_7") (pintype "passive"))
      (node (ref "J3") (pin "1") (pinfunction "1_1") (pintype "passive"))
      (node (ref "J3") (pin "12") (pinfunction "12_12") (pintype "passive"))
      (node (ref "J3") (pin "15") (pinfunction "15_15") (pintype "passive"))
      (node (ref "J3") (pin "16") (pinfunction "16_16") (pintype "passive"))
      (node (ref "J3") (pin "2") (pinfunction "2_2") (pintype "passive"))
      (node (ref "J3") (pin "3") (pinfunction "3_3") (pintype "passive"))
      (node (ref "J3") (pin "4") (pinfunction "4_4") (pintype "passive"))
      (node (ref "J5") (pin "2") (pinfunction "2_2") (pintype "passive"))
      (node (ref "J5") (pin "4") (pinfunction "4_4") (pintype "passive"))
      (node (ref "P2") (pin "4") (pintype "passive"))
      (node (ref "P2") (pin "5") (pintype "passive"))
      (node (ref "R1") (pin "2") (pinfunction "2_2") (pintype "passive"))
      (node (ref "R14") (pin "2") (pinfunction "2_2") (pintype "passive"))
      (node (ref "R2") (pin "1") (pinfunction "1_1") (pintype "passive"))
      (node (ref "R22") (pin "2") (pinfunction "2_2") (pintype "passive"))
      (node (ref "R24") (pin "2") (pinfunction "2_2") (pintype "passive"))
      (node (ref "R28") (pin "1") (pintype "passive"))
      (node (ref "R29") (pin "1") (pintype "passive"))
      (node (ref "R3") (pin "1") (pinfunction "1_1") (pintype "passive"))
      (node (ref "S3") (pin "3") (pinfunction "3_3") (pintype "passive"))
      (node (ref "U2") (pin "11") (pinfunction "VDD_5_11") (pintype "power_in"))
      (node (ref "U2") (pin "28") (pinfunction "VDD_4_28") (pintype "power_in"))
      (node (ref "U2") (pin "75") (pinfunction "VDD_2_75") (pintype "power_in"))
      (node (ref "U3") (pin "14") (pinfunction "VDD33/VIO_14") (pintype "power_in"))
    )
    (net (code "121") (name "5V_in") (class "Default")
      (node (ref "F2") (pin "1") (pinfunction "1_1") (pintype "passive"))
      (node (ref "P6") (pin "A4") (pinfunction "VBUS_A4") (pintype "bidirectional"))
      (node (ref "P6") (pin "B4") (pinfunction "VBUS_B4") (pintype "bidirectional"))
      (node (ref "P7") (pin "A4") (pinfunction "VBUS_A4") (pintype "bidirectional"))
      (node (ref "P7") (pin "B4") (pinfunction "VBUS_B4") (pintype "bidirectional"))
      (node (ref "P9") (pin "A4") (pinfunction "VBUS_A4") (pintype "bidirectional"))
      (node (ref "P9") (pin "B4") (pinfunction "VBUS_B4") (pintype "bidirectional"))
    )
    (net (code "122") (name "GND") (class "Default")
      (node (ref "C1") (pin "1") (pinfunction "1_1") (pintype "passive"))
      (node (ref "C10") (pin "1") (pinfunction "1_1") (pintype "passive"))
      (node (ref "C11") (pin "1") (pinfunction "1_1") (pintype "passive"))
      (node (ref "C12") (pin "2") (pinfunction "2_2") (pintype "passive"))
      (node (ref "C13") (pin "2") (pinfunction "2_2") (pintype "passive"))
      (node (ref "C14") (pin "1") (pinfunction "1_1") (pintype "passive"))
      (node (ref "C2") (pin "1") (pinfunction "1_1") (pintype "passive"))
      (node (ref "C21") (pin "2") (pinfunction "2_2") (pintype "passive"))
      (node (ref "C3") (pin "2") (pinfunction "2_2") (pintype "passive"))
      (node (ref "C31") (pin "1") (pinfunction "1_1") (pintype "passive"))
      (node (ref "C32") (pin "1") (pinfunction "1_1") (pintype "passive"))
      (node (ref "C4") (pin "1") (pinfunction "1_1") (pintype "passive"))
      (node (ref "C46") (pin "2") (pinfunction "2_2") (pintype "passive"))
      (node (ref "C5") (pin "2") (pinfunction "2_2") (pintype "passive"))
      (node (ref "C6") (pin "2") (pinfunction "2_2") (pintype "passive"))
      (node (ref "C7") (pin "1") (pinfunction "1_1") (pintype "passive"))
      (node (ref "C8") (pin "1") (pinfunction "1_1") (pintype "passive"))
      (node (ref "C9") (pin "1") (pinfunction "1_1") (pintype "passive"))
      (node (ref "J2") (pin "5") (pinfunction "5_5") (pintype "passive"))
      (node (ref "J2") (pin "6") (pinfunction "6_6") (pintype "passive"))
      (node (ref "J3") (pin "20") (pinfunction "20_20") (pintype "passive"))
      (node (ref "J3") (pin "22") (pinfunction "22_22") (pintype "passive"))
      (node (ref "J3") (pin "25") (pinfunction "25_25") (pintype "passive"))
      (node (ref "J3") (pin "26") (pinfunction "26_26") (pintype "passive"))
      (node (ref "J3") (pin "7") (pinfunction "7_7") (pintype "passive"))
      (node (ref "J3") (pin "8") (pinfunction "8_8") (pintype "passive"))
      (node (ref "J3") (pin "9") (pinfunction "9_9") (pintype "passive"))
      (node (ref "J4") (pin "7") (pinfunction "7_7") (pintype "passive"))
      (node (ref "J5") (pin "6") (pinfunction "6_6") (pintype "passive"))
      (node (ref "J5") (pin "7") (pinfunction "7_7") (pintype "passive"))
      (node (ref "J7") (pin "4") (pinfunction "4_4") (pintype "passive"))
      (node (ref "P2") (pin "8") (pintype "passive"))
      (node (ref "P6") (pin "A1") (pinfunction "GND_A1") (pintype "bidirectional"))
      (node (ref "P6") (pin "B1") (pinfunction "GND_B1") (pintype "bidirectional"))
      (node (ref "P7") (pin "A1") (pinfunction "GND_A1") (pintype "bidirectional"))
      (node (ref "P7") (pin "B1") (pinfunction "GND_B1") (pintype "bidirectional"))
      (node (ref "P9") (pin "A1") (pinfunction "GND_A1") (pintype "bidirectional"))
      (node (ref "P9") (pin "B1") (pinfunction "GND_B1") (pintype "bidirectional"))
      (node (ref "PWR") (pin "2") (pinfunction "K_2") (pintype "passive"))
      (node (ref "R10") (pin "2") (pinfunction "2_2") (pintype "passive"))
      (node (ref "R11") (pin "2") (pinfunction "2_2") (pintype "passive"))
      (node (ref "R18") (pin "1") (pinfunction "1_1") (pintype "passive"))
      (node (ref "R20") (pin "1") (pinfunction "1_1") (pintype "passive"))
      (node (ref "R21") (pin "1") (pinfunction "1_1") (pintype "passive"))
      (node (ref "R31") (pin "1") (pinfunction "1_1") (pintype "passive"))
      (node (ref "R8") (pin "1") (pinfunction "1_1") (pintype "passive"))
      (node (ref "R9") (pin "1") (pinfunction "1_1") (pintype "passive"))
      (node (ref "S1") (pin "3") (pinfunction "B1_3") (pintype "passive"))
      (node (ref "S2") (pin "3") (pinfunction "B1_3") (pintype "passive"))
      (node (ref "S5") (pin "2") (pinfunction "2_2") (pintype "passive"))
      (node (ref "U1") (pin "1") (pinfunction "GND_1") (pintype "passive"))
      (node (ref "U2") (pin "10") (pinfunction "VSS_5_10") (pintype "power_in"))
      (node (ref "U2") (pin "19") (pinfunction "VSSA_19") (pintype "power_in"))
      (node (ref "U2") (pin "27") (pinfunction "VSS_4_27") (pintype "power_in"))
      (node (ref "U2") (pin "49") (pinfunction "VSS_1_49") (pintype "power_in"))
      (node (ref "U2") (pin "74") (pinfunction "VSS_2_74") (pintype "power_in"))
      (node (ref "U2") (pin "99") (pinfunction "VSS_3_99") (pintype "power_in"))
      (node (ref "U3") (pin "18") (pinfunction "VSS/GND_18") (pintype "power_in"))
    )
    (net (code "123") (name "Net-(D2-K)") (class "Default")
      (node (ref "D2") (pin "2") (pinfunction "K_2") (pintype "passive"))
      (node (ref "R13") (pin "2") (pinfunction "2_2") (pintype "passive"))
    )
    (net (code "124") (name "Net-(D3-K)") (class "Default")
      (node (ref "D3") (pin "2") (pinfunction "K_2") (pintype "passive"))
      (node (ref "R21") (pin "2") (pinfunction "2_2") (pintype "passive"))
    )
    (net (code "125") (name "Net-(J3-Pad6)") (class "Default")
      (node (ref "J3") (pin "6") (pinfunction "6_6") (pintype "passive"))
      (node (ref "R5") (pin "1") (pinfunction "1_1") (pintype "passive"))
    )
    (net (code "126") (name "Net-(J3-Pad10)") (class "Default")
      (node (ref "J3") (pin "10") (pinfunction "10_10") (pintype "passive"))
      (node (ref "J5") (pin "1") (pinfunction "1_1") (pintype "passive"))
    )
    (net (code "127") (name "Net-(LED1-A)") (class "Default")
      (node (ref "LED1") (pin "1") (pinfunction "A_1") (pintype "passive"))
      (node (ref "R2") (pin "2") (pinfunction "2_2") (pintype "passive"))
    )
    (net (code "128") (name "Net-(LED2-A)") (class "Default")
      (node (ref "LED2") (pin "1") (pinfunction "A_1") (pintype "passive"))
      (node (ref "R3") (pin "2") (pinfunction "2_2") (pintype "passive"))
    )
    (net (code "129") (name "Net-(P2-Pad9)") (class "Default")
      (node (ref "P2") (pin "9") (pintype "passive"))
      (node (ref "R28") (pin "2") (pintype "passive"))
    )
    (net (code "130") (name "Net-(P2-Pad12)") (class "Default")
      (node (ref "P2") (pin "12") (pintype "passive"))
      (node (ref "R29") (pin "2") (pintype "passive"))
    )
    (net (code "131") (name "Net-(P6-CC-PadA5)") (class "Default")
      (node (ref "P6") (pin "A5") (pinfunction "CC_A5") (pintype "bidirectional"))
      (node (ref "R20") (pin "2") (pinfunction "2_2") (pintype "passive"))
    )
    (net (code "132") (name "Net-(P6-CC-PadB5)") (class "Default")
      (node (ref "P6") (pin "B5") (pinfunction "CC_B5") (pintype "bidirectional"))
      (node (ref "R31") (pin "2") (pinfunction "2_2") (pintype "passive"))
    )
    (net (code "133") (name "Net-(P7-CC-PadA5)") (class "Default")
      (node (ref "P7") (pin "A5") (pinfunction "CC_A5") (pintype "bidirectional"))
      (node (ref "R8") (pin "2") (pinfunction "2_2") (pintype "passive"))
    )
    (net (code "134") (name "Net-(P7-CC-PadB5)") (class "Default")
      (node (ref "P7") (pin "B5") (pinfunction "CC_B5") (pintype "bidirectional"))
      (node (ref "R9") (pin "2") (pinfunction "2_2") (pintype "passive"))
    )
    (net (code "135") (name "Net-(P9-CC-PadA5)") (class "Default")
      (node (ref "P9") (pin "A5") (pinfunction "CC_A5") (pintype "bidirectional"))
      (node (ref "R10") (pin "1") (pinfunction "1_1") (pintype "passive"))
    )
    (net (code "136") (name "Net-(P9-CC-PadB5)") (class "Default")
      (node (ref "P9") (pin "B5") (pinfunction "CC_B5") (pintype "bidirectional"))
      (node (ref "R11") (pin "1") (pinfunction "1_1") (pintype "passive"))
    )
    (net (code "137") (name "Net-(PWR-A)") (class "Default")
      (node (ref "PWR") (pin "1") (pinfunction "A_1") (pintype "passive"))
      (node (ref "R1") (pin "1") (pinfunction "1_1") (pintype "passive"))
    )
    (net (code "138") (name "Net-(U1-VOUT)") (class "Default")
      (node (ref "C13") (pin "1") (pinfunction "1_1") (pintype "passive"))
      (node (ref "S3") (pin "1") (pinfunction "1_1") (pintype "passive"))
      (node (ref "U1") (pin "2") (pinfunction "VOUT_2") (pintype "passive"))
    )
    (net (code "139") (name "unconnected-(P2-Pad7)") (class "Default")
      (node (ref "P2") (pin "7") (pintype "passive"))
    )
    (net (code "140") (name "unconnected-(P6-RFU1-PadA8)") (class "Default")
      (node (ref "P6") (pin "A8") (pinfunction "RFU1_A8") (pintype "bidirectional+no_connect"))
    )
    (net (code "141") (name "unconnected-(P6-RFU1-PadB8)") (class "Default")
      (node (ref "P6") (pin "B8") (pinfunction "RFU1_B8") (pintype "bidirectional+no_connect"))
    )
    (net (code "142") (name "unconnected-(P7-RFU1-PadA8)") (class "Default")
      (node (ref "P7") (pin "A8") (pinfunction "RFU1_A8") (pintype "bidirectional+no_connect"))
    )
    (net (code "143") (name "unconnected-(P7-RFU1-PadB8)") (class "Default")
      (node (ref "P7") (pin "B8") (pinfunction "RFU1_B8") (pintype "bidirectional+no_connect"))
    )
    (net (code "144") (name "unconnected-(P9-RFU1-PadA8)") (class "Default")
      (node (ref "P9") (pin "A8") (pinfunction "RFU1_A8") (pintype "bidirectional+no_connect"))
    )
    (net (code "145") (name "unconnected-(P9-RFU1-PadB8)") (class "Default")
      (node (ref "P9") (pin "B8") (pinfunction "RFU1_B8") (pintype "bidirectional+no_connect"))
    )
    (net (code "146") (name "unconnected-(S1-A1-Pad4)") (class "Default")
      (node (ref "S1") (pin "4") (pinfunction "A1_4") (pintype "passive"))
    )
    (net (code "147") (name "unconnected-(S1-B0-Pad2)") (class "Default")
      (node (ref "S1") (pin "2") (pinfunction "B0_2") (pintype "passive"))
    )
    (net (code "148") (name "unconnected-(S2-A1-Pad4)") (class "Default")
      (node (ref "S2") (pin "4") (pinfunction "A1_4") (pintype "passive"))
    )
    (net (code "149") (name "unconnected-(S2-B0-Pad2)") (class "Default")
      (node (ref "S2") (pin "2") (pinfunction "B0_2") (pintype "passive"))
    )
    (net (code "150") (name "unconnected-(S3-Pad2)") (class "Default")
      (node (ref "S3") (pin "2") (pinfunction "2_2") (pintype "passive"))
    )
    (net (code "151") (name "unconnected-(U3-PA5{slash}UART1_CTS{slash}PA1_(no5V)-Pad2)") (class "Default")
      (node (ref "U3") (pin "2") (pinfunction "PA5/UART1_CTS/PA1_(no5V)_2") (pintype "bidirectional+no_connect"))
    )
    (net (code "152") (name "unconnected-(U3-PB12{slash}SPI2_NSS{slash}CAN2_RX-Pad5)") (class "Default")
      (node (ref "U3") (pin "5") (pinfunction "PB12/SPI2_NSS/CAN2_RX_5") (pintype "bidirectional+no_connect"))
    )
    (net (code "153") (name "unconnected-(U3-PB14{slash}SPI2_MISO{slash}UART3_RTS-Pad7)") (class "Default")
      (node (ref "U3") (pin "7") (pinfunction "PB14/SPI2_MISO/UART3_RTS_7") (pintype "bidirectional+no_connect"))
    )
    (net (code "154") (name "unconnected-(U3-PB15{slash}SPI2_MOSI{slash}UART1_TX-Pad8)") (class "Default")
      (node (ref "U3") (pin "8") (pinfunction "PB15/SPI2_MOSI/UART1_TX_8") (pintype "bidirectional+no_connect"))
    )
  )
)
